# LineOut_Headphone.net
KiCad netlist of a schematic drawn in EAGLE
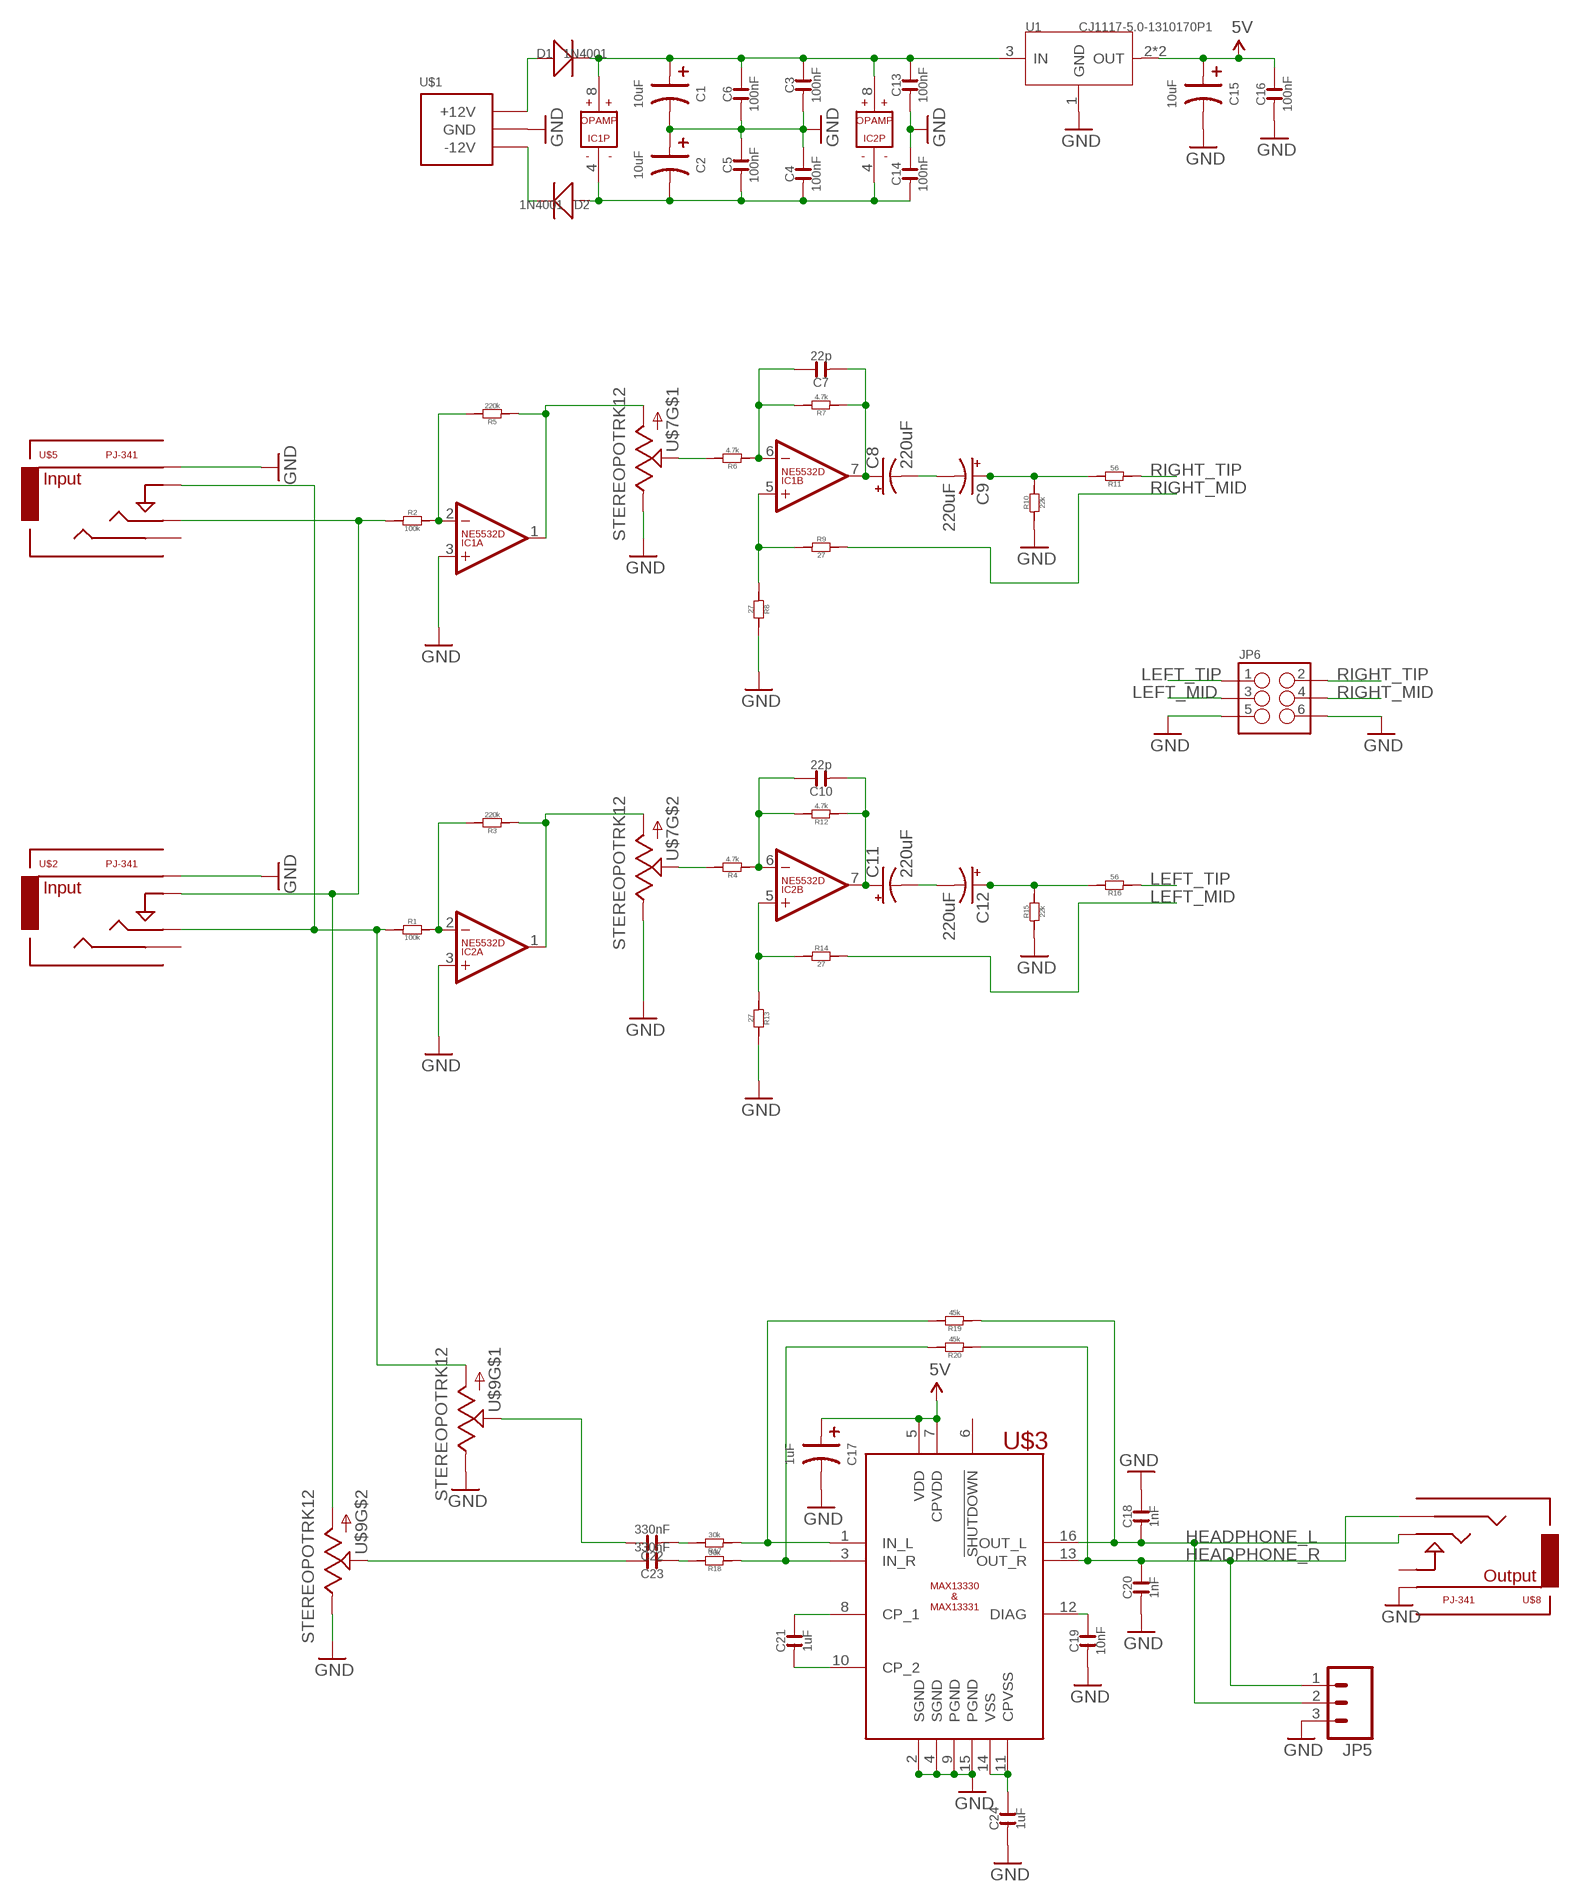
[diagram p0: schematic, sheet 1]

(export (version "E")
  (design (tool "Eeschema 10.0.6"))
  (components
    (comp (ref "C1")
      (value "10uF")
      (footprint "eagle-import:CASE-A_3216")
      (libsource (lib "eagle-import") (part "C-POLAR-A"))
    )
    (comp (ref "C2")
      (value "10uF")
      (footprint "eagle-import:CASE-A_3216")
      (libsource (lib "eagle-import") (part "C-POLAR-A"))
    )
    (comp (ref "C3")
      (value "100nF")
      (footprint "eagle-import:C0603")
      (libsource (lib "eagle-import") (part "C-0603"))
    )
    (comp (ref "C4")
      (value "100nF")
      (footprint "eagle-import:C0603")
      (libsource (lib "eagle-import") (part "C-0603"))
    )
    (comp (ref "C5")
      (value "100nF")
      (footprint "eagle-import:C0603")
      (libsource (lib "eagle-import") (part "C-0603"))
    )
    (comp (ref "C6")
      (value "100nF")
      (footprint "eagle-import:C0603")
      (libsource (lib "eagle-import") (part "C-0603"))
    )
    (comp (ref "C7")
      (value "22p")
      (footprint "eagle-import:C0603")
      (libsource (lib "eagle-import") (part "C-0603"))
    )
    (comp (ref "C8")
      (value "220uF")
      (footprint "eagle-import:153CLV-0505")
      (libsource (lib "eagle-import") (part "CPOL-US153CLV-0505"))
    )
    (comp (ref "C9")
      (value "220uF")
      (footprint "eagle-import:153CLV-0505")
      (libsource (lib "eagle-import") (part "CPOL-US153CLV-0505"))
    )
    (comp (ref "C10")
      (value "22p")
      (footprint "eagle-import:C0603")
      (libsource (lib "eagle-import") (part "C-0603"))
    )
    (comp (ref "C11")
      (value "220uF")
      (footprint "eagle-import:153CLV-0505")
      (libsource (lib "eagle-import") (part "CPOL-US153CLV-0505"))
    )
    (comp (ref "C12")
      (value "220uF")
      (footprint "eagle-import:153CLV-0505")
      (libsource (lib "eagle-import") (part "CPOL-US153CLV-0505"))
    )
    (comp (ref "C13")
      (value "100nF")
      (footprint "eagle-import:C0603")
      (libsource (lib "eagle-import") (part "C-0603"))
    )
    (comp (ref "C14")
      (value "100nF")
      (footprint "eagle-import:C0603")
      (libsource (lib "eagle-import") (part "C-0603"))
    )
    (comp (ref "C15")
      (value "10uF")
      (footprint "eagle-import:CASE-A_3216")
      (libsource (lib "eagle-import") (part "C-POLAR-A"))
    )
    (comp (ref "C16")
      (value "100nF")
      (footprint "eagle-import:C0603")
      (libsource (lib "eagle-import") (part "C-0603"))
    )
    (comp (ref "C17")
      (value "1uF")
      (footprint "eagle-import:CASE-A_3216")
      (libsource (lib "eagle-import") (part "C-POLAR-A"))
    )
    (comp (ref "C18")
      (value "1nF")
      (footprint "eagle-import:C0603")
      (libsource (lib "eagle-import") (part "C-0603"))
    )
    (comp (ref "C19")
      (value "10nF")
      (footprint "eagle-import:C0603")
      (libsource (lib "eagle-import") (part "C-0603"))
    )
    (comp (ref "C20")
      (value "1nF")
      (footprint "eagle-import:C0603")
      (libsource (lib "eagle-import") (part "C-0603"))
    )
    (comp (ref "C21")
      (value "1uF")
      (footprint "eagle-import:C0603")
      (libsource (lib "eagle-import") (part "C-0603"))
    )
    (comp (ref "C22")
      (value "330nF")
      (footprint "eagle-import:C0603")
      (libsource (lib "eagle-import") (part "C-0603"))
    )
    (comp (ref "C23")
      (value "330nF")
      (footprint "eagle-import:C0603")
      (libsource (lib "eagle-import") (part "C-0603"))
    )
    (comp (ref "C24")
      (value "1uF")
      (footprint "eagle-import:C0603")
      (libsource (lib "eagle-import") (part "C-0603"))
    )
    (comp (ref "D1")
      (value "1N4001")
      (footprint "eagle-import:SOD123")
      (libsource (lib "eagle-import") (part "D-SOD-123"))
    )
    (comp (ref "D2")
      (value "1N4001")
      (footprint "eagle-import:SOD123")
      (libsource (lib "eagle-import") (part "D-SOD-123"))
    )
    (comp (ref "IC1")
      (value "NE5532D")
      (footprint "eagle-import:SO08")
      (libsource (lib "eagle-import") (part "NE5532D"))
    )
    (comp (ref "IC2")
      (value "NE5532D")
      (footprint "eagle-import:SO08")
      (libsource (lib "eagle-import") (part "NE5532D"))
    )
    (comp (ref "JP5")
      (value "M03PTH")
      (footprint "eagle-import:1X03")
      (libsource (lib "eagle-import") (part "M03PTH"))
    )
    (comp (ref "JP6")
      (value "M03X2")
      (footprint "eagle-import:2X3-SHROUDED")
      (libsource (lib "eagle-import") (part "M03X2"))
    )
    (comp (ref "R1")
      (value "100k")
      (footprint "eagle-import:R0603")
      (libsource (lib "eagle-import") (part "R-0603"))
    )
    (comp (ref "R2")
      (value "100k")
      (footprint "eagle-import:R0603")
      (libsource (lib "eagle-import") (part "R-0603"))
    )
    (comp (ref "R3")
      (value "220k")
      (footprint "eagle-import:R0603")
      (libsource (lib "eagle-import") (part "R-0603"))
    )
    (comp (ref "R4")
      (value "4.7k")
      (footprint "eagle-import:R0603")
      (libsource (lib "eagle-import") (part "R-0603"))
    )
    (comp (ref "R5")
      (value "220k")
      (footprint "eagle-import:R0603")
      (libsource (lib "eagle-import") (part "R-0603"))
    )
    (comp (ref "R6")
      (value "4.7k")
      (footprint "eagle-import:R0603")
      (libsource (lib "eagle-import") (part "R-0603"))
    )
    (comp (ref "R7")
      (value "4.7k")
      (footprint "eagle-import:R0603")
      (libsource (lib "eagle-import") (part "R-0603"))
    )
    (comp (ref "R8")
      (value "27")
      (footprint "eagle-import:R0603")
      (libsource (lib "eagle-import") (part "R-0603"))
    )
    (comp (ref "R9")
      (value "27")
      (footprint "eagle-import:R0603")
      (libsource (lib "eagle-import") (part "R-0603"))
    )
    (comp (ref "R10")
      (value "22k")
      (footprint "eagle-import:R0603")
      (libsource (lib "eagle-import") (part "R-0603"))
    )
    (comp (ref "R11")
      (value "56")
      (footprint "eagle-import:R0603")
      (libsource (lib "eagle-import") (part "R-0603"))
    )
    (comp (ref "R12")
      (value "4.7k")
      (footprint "eagle-import:R0603")
      (libsource (lib "eagle-import") (part "R-0603"))
    )
    (comp (ref "R13")
      (value "27")
      (footprint "eagle-import:R0603")
      (libsource (lib "eagle-import") (part "R-0603"))
    )
    (comp (ref "R14")
      (value "27")
      (footprint "eagle-import:R0603")
      (libsource (lib "eagle-import") (part "R-0603"))
    )
    (comp (ref "R15")
      (value "22k")
      (footprint "eagle-import:R0603")
      (libsource (lib "eagle-import") (part "R-0603"))
    )
    (comp (ref "R16")
      (value "56")
      (footprint "eagle-import:R0603")
      (libsource (lib "eagle-import") (part "R-0603"))
    )
    (comp (ref "R17")
      (value "30k")
      (footprint "eagle-import:R0603")
      (libsource (lib "eagle-import") (part "R-0603"))
    )
    (comp (ref "R18")
      (value "30k")
      (footprint "eagle-import:R0603")
      (libsource (lib "eagle-import") (part "R-0603"))
    )
    (comp (ref "R19")
      (value "45k")
      (footprint "eagle-import:R0603")
      (libsource (lib "eagle-import") (part "R-0603"))
    )
    (comp (ref "R20")
      (value "45k")
      (footprint "eagle-import:R0603")
      (libsource (lib "eagle-import") (part "R-0603"))
    )
    (comp (ref "U$1")
      (value "POWER_SIMPLE10")
      (footprint "eagle-import:POWER_10")
      (libsource (lib "eagle-import") (part "POWER_SIMPLE10"))
    )
    (comp (ref "U$2")
      (value "PJ-341")
      (footprint "eagle-import:3.5MM-JACK-SWITCH-13MM-INPUT")
      (libsource (lib "eagle-import") (part "AUDIO-JACKINPUT"))
    )
    (comp (ref "U$3")
      (value "MAX13330")
      (footprint "eagle-import:QSOP16")
      (libsource (lib "eagle-import") (part "MAX13330"))
    )
    (comp (ref "U$5")
      (value "PJ-341")
      (footprint "eagle-import:3.5MM-JACK-SWITCH-13MM-INPUT")
      (libsource (lib "eagle-import") (part "AUDIO-JACKINPUT"))
    )
    (comp (ref "U$7")
      (value "STEREOPOTRK12")
      (footprint "eagle-import:RK12")
      (libsource (lib "eagle-import") (part "STEREOPOTRK12"))
    )
    (comp (ref "U$8")
      (value "PJ-341")
      (footprint "eagle-import:3.5MM-JACK-SWITCH-13MM-OUTPUT")
      (libsource (lib "eagle-import") (part "AUDIO-JACKOUTPUT"))
    )
    (comp (ref "U$9")
      (value "STEREOPOTRK12")
      (footprint "eagle-import:RK12")
      (libsource (lib "eagle-import") (part "STEREOPOTRK12"))
    )
    (comp (ref "U1")
      (value "CJ1117-5.0-1310170P1")
      (footprint "eagle-import:SOT223")
      (libsource (lib "eagle-import") (part "CJ1117-5.0-1310170P1"))
    )
  )
  (nets
    (net (code "1") (name "/HEADPHONE_L") (class "Default")
      (node (ref "C18") (pin "1") (pinfunction "1_1") (pintype "bidirectional"))
      (node (ref "JP5") (pin "2") (pinfunction "2_2") (pintype "passive"))
      (node (ref "R19") (pin "1") (pinfunction "1_1") (pintype "bidirectional"))
      (node (ref "U$3") (pin "16") (pinfunction "OUT_L_16") (pintype "bidirectional"))
      (node (ref "U$8") (pin "TIP@3") (pinfunction "TIP_TIP@3") (pintype "bidirectional"))
    )
    (net (code "2") (name "/HEADPHONE_R") (class "Default")
      (node (ref "C20") (pin "2") (pinfunction "2_2") (pintype "bidirectional"))
      (node (ref "JP5") (pin "1") (pinfunction "1_1") (pintype "passive"))
      (node (ref "R20") (pin "1") (pinfunction "1_1") (pintype "bidirectional"))
      (node (ref "U$3") (pin "13") (pinfunction "OUT_R_13") (pintype "bidirectional"))
      (node (ref "U$8") (pin "SECOND@3") (pinfunction "SECOND_SECOND@3") (pintype "bidirectional"))
    )
    (net (code "3") (name "/LEFT_MID") (class "Default")
      (node (ref "JP6") (pin "3") (pinfunction "3_3") (pintype "bidirectional"))
      (node (ref "R14") (pin "2") (pinfunction "2_2") (pintype "bidirectional"))
    )
    (net (code "4") (name "/LEFT_TIP") (class "Default")
      (node (ref "JP6") (pin "1") (pinfunction "1_1") (pintype "bidirectional"))
      (node (ref "R16") (pin "1") (pinfunction "1_1") (pintype "bidirectional"))
    )
    (net (code "5") (name "/RIGHT_MID") (class "Default")
      (node (ref "JP6") (pin "4") (pinfunction "4_4") (pintype "bidirectional"))
      (node (ref "R9") (pin "2") (pinfunction "2_2") (pintype "bidirectional"))
    )
    (net (code "6") (name "/RIGHT_TIP") (class "Default")
      (node (ref "JP6") (pin "2") (pinfunction "2_2") (pintype "bidirectional"))
      (node (ref "R11") (pin "1") (pinfunction "1_1") (pintype "bidirectional"))
    )
    (net (code "7") (name "5V") (class "Default")
      (node (ref "C15") (pin "+") (pinfunction "1_+") (pintype "bidirectional"))
      (node (ref "C16") (pin "2") (pinfunction "2_2") (pintype "bidirectional"))
      (node (ref "C17") (pin "+") (pinfunction "1_+") (pintype "bidirectional"))
      (node (ref "U$3") (pin "5") (pinfunction "VDD_5") (pintype "bidirectional"))
      (node (ref "U$3") (pin "7") (pinfunction "CPVDD_7") (pintype "bidirectional"))
      (node (ref "U1") (pin "2") (pinfunction "OUT_2") (pintype "bidirectional"))
      (node (ref "U1") (pin "TER") (pinfunction "OUT_TER") (pintype "bidirectional"))
    )
    (net (code "8") (name "GND") (class "Default")
      (node (ref "C1") (pin "-") (pinfunction "2_-") (pintype "bidirectional"))
      (node (ref "C13") (pin "1") (pinfunction "1_1") (pintype "bidirectional"))
      (node (ref "C14") (pin "2") (pinfunction "2_2") (pintype "bidirectional"))
      (node (ref "C15") (pin "-") (pinfunction "2_-") (pintype "bidirectional"))
      (node (ref "C16") (pin "1") (pinfunction "1_1") (pintype "bidirectional"))
      (node (ref "C17") (pin "-") (pinfunction "2_-") (pintype "bidirectional"))
      (node (ref "C18") (pin "2") (pinfunction "2_2") (pintype "bidirectional"))
      (node (ref "C19") (pin "1") (pinfunction "1_1") (pintype "bidirectional"))
      (node (ref "C2") (pin "+") (pinfunction "1_+") (pintype "bidirectional"))
      (node (ref "C20") (pin "1") (pinfunction "1_1") (pintype "bidirectional"))
      (node (ref "C24") (pin "1") (pinfunction "1_1") (pintype "bidirectional"))
      (node (ref "C3") (pin "1") (pinfunction "1_1") (pintype "bidirectional"))
      (node (ref "C4") (pin "2") (pinfunction "2_2") (pintype "bidirectional"))
      (node (ref "C5") (pin "2") (pinfunction "2_2") (pintype "bidirectional"))
      (node (ref "C6") (pin "1") (pinfunction "1_1") (pintype "bidirectional"))
      (node (ref "IC1") (pin "3") (pinfunction "+IN_3") (pintype "input"))
      (node (ref "IC2") (pin "3") (pinfunction "+IN_3") (pintype "input"))
      (node (ref "JP5") (pin "3") (pinfunction "3_3") (pintype "passive"))
      (node (ref "JP6") (pin "5") (pinfunction "5_5") (pintype "bidirectional"))
      (node (ref "JP6") (pin "6") (pinfunction "6_6") (pintype "bidirectional"))
      (node (ref "R10") (pin "1") (pinfunction "1_1") (pintype "bidirectional"))
      (node (ref "R13") (pin "2") (pinfunction "2_2") (pintype "bidirectional"))
      (node (ref "R15") (pin "1") (pinfunction "1_1") (pintype "bidirectional"))
      (node (ref "R8") (pin "2") (pinfunction "2_2") (pintype "bidirectional"))
      (node (ref "U$1") (pin "3") (pinfunction "GND_3") (pintype "bidirectional"))
      (node (ref "U$1") (pin "4") (pinfunction "GND_4") (pintype "bidirectional"))
      (node (ref "U$1") (pin "5") (pinfunction "GND_5") (pintype "bidirectional"))
      (node (ref "U$1") (pin "6") (pinfunction "GND_6") (pintype "bidirectional"))
      (node (ref "U$1") (pin "7") (pinfunction "GND_7") (pintype "bidirectional"))
      (node (ref "U$1") (pin "8") (pinfunction "GND_8") (pintype "bidirectional"))
      (node (ref "U$2") (pin "RING@3") (pinfunction "RING_RING@3") (pintype "bidirectional"))
      (node (ref "U$3") (pin "15") (pinfunction "PGND_15") (pintype "bidirectional"))
      (node (ref "U$3") (pin "2") (pinfunction "SGND_2") (pintype "bidirectional"))
      (node (ref "U$3") (pin "4") (pinfunction "SGND_4") (pintype "bidirectional"))
      (node (ref "U$3") (pin "9") (pinfunction "PGND_9") (pintype "bidirectional"))
      (node (ref "U$5") (pin "RING@3") (pinfunction "RING_RING@3") (pintype "bidirectional"))
      (node (ref "U$7") (pin "R1_1") (pinfunction "E_R1_1") (pintype "passive"))
      (node (ref "U$7") (pin "R2_1") (pinfunction "E_R2_1") (pintype "passive"))
      (node (ref "U$8") (pin "RING@3") (pinfunction "RING_RING@3") (pintype "bidirectional"))
      (node (ref "U$9") (pin "R1_1") (pinfunction "E_R1_1") (pintype "passive"))
      (node (ref "U$9") (pin "R2_1") (pinfunction "E_R2_1") (pintype "passive"))
      (node (ref "U1") (pin "1") (pinfunction "GND_1") (pintype "bidirectional"))
    )
    (net (code "9") (name "Net-(C1-1)") (class "Default")
      (node (ref "C1") (pin "+") (pinfunction "1_+") (pintype "bidirectional"))
      (node (ref "C13") (pin "2") (pinfunction "2_2") (pintype "bidirectional"))
      (node (ref "C3") (pin "2") (pinfunction "2_2") (pintype "bidirectional"))
      (node (ref "C6") (pin "2") (pinfunction "2_2") (pintype "bidirectional"))
      (node (ref "D1") (pin "-") (pinfunction "-_-") (pintype "passive"))
      (node (ref "IC1") (pin "8") (pinfunction "V+_8") (pintype "power_in"))
      (node (ref "IC2") (pin "8") (pinfunction "V+_8") (pintype "power_in"))
      (node (ref "U1") (pin "3") (pinfunction "IN_3") (pintype "bidirectional"))
    )
    (net (code "10") (name "Net-(C2-2)") (class "Default")
      (node (ref "C14") (pin "1") (pinfunction "1_1") (pintype "bidirectional"))
      (node (ref "C2") (pin "-") (pinfunction "2_-") (pintype "bidirectional"))
      (node (ref "C4") (pin "1") (pinfunction "1_1") (pintype "bidirectional"))
      (node (ref "C5") (pin "1") (pinfunction "1_1") (pintype "bidirectional"))
      (node (ref "D2") (pin "+") (pinfunction "+_+") (pintype "passive"))
      (node (ref "IC1") (pin "4") (pinfunction "V-_4") (pintype "power_in"))
      (node (ref "IC2") (pin "4") (pinfunction "V-_4") (pintype "power_in"))
    )
    (net (code "11") (name "Net-(C8-Pad-)") (class "Default")
      (node (ref "C8") (pin "-") (pinfunction "-_-") (pintype "passive"))
      (node (ref "C9") (pin "-") (pinfunction "-_-") (pintype "passive"))
    )
    (net (code "12") (name "Net-(C9-Pad+)") (class "Default")
      (node (ref "C9") (pin "+") (pinfunction "+_+") (pintype "passive"))
      (node (ref "R10") (pin "2") (pinfunction "2_2") (pintype "bidirectional"))
      (node (ref "R11") (pin "2") (pinfunction "2_2") (pintype "bidirectional"))
    )
    (net (code "13") (name "Net-(C11-Pad-)") (class "Default")
      (node (ref "C11") (pin "-") (pinfunction "-_-") (pintype "passive"))
      (node (ref "C12") (pin "-") (pinfunction "-_-") (pintype "passive"))
    )
    (net (code "14") (name "Net-(C12-Pad+)") (class "Default")
      (node (ref "C12") (pin "+") (pinfunction "+_+") (pintype "passive"))
      (node (ref "R15") (pin "2") (pinfunction "2_2") (pintype "bidirectional"))
      (node (ref "R16") (pin "2") (pinfunction "2_2") (pintype "bidirectional"))
    )
    (net (code "15") (name "Net-(C22-Pad1)") (class "Default")
      (node (ref "C22") (pin "1") (pinfunction "1_1") (pintype "bidirectional"))
      (node (ref "R17") (pin "2") (pinfunction "2_2") (pintype "bidirectional"))
    )
    (net (code "16") (name "Net-(C23-Pad1)") (class "Default")
      (node (ref "C23") (pin "1") (pinfunction "1_1") (pintype "bidirectional"))
      (node (ref "R18") (pin "2") (pinfunction "2_2") (pintype "bidirectional"))
    )
    (net (code "17") (name "Net-(D1-Pad+)") (class "Default")
      (node (ref "D1") (pin "+") (pinfunction "+_+") (pintype "passive"))
      (node (ref "U$1") (pin "10") (pinfunction "+12V_10") (pintype "bidirectional"))
      (node (ref "U$1") (pin "9") (pinfunction "+12V_9") (pintype "bidirectional"))
    )
    (net (code "18") (name "Net-(D2-Pad-)") (class "Default")
      (node (ref "D2") (pin "-") (pinfunction "-_-") (pintype "passive"))
      (node (ref "U$1") (pin "1") (pinfunction "-12V_1") (pintype "bidirectional"))
      (node (ref "U$1") (pin "2") (pinfunction "-12V_2") (pintype "bidirectional"))
    )
    (net (code "19") (name "Net-(IC1A--IN)") (class "Default")
      (node (ref "IC1") (pin "2") (pinfunction "-IN_2") (pintype "input"))
      (node (ref "R2") (pin "2") (pinfunction "2_2") (pintype "bidirectional"))
      (node (ref "R5") (pin "2") (pinfunction "2_2") (pintype "bidirectional"))
    )
    (net (code "20") (name "Net-(IC1A-OUT)") (class "Default")
      (node (ref "IC1") (pin "1") (pinfunction "OUT_1") (pintype "output"))
      (node (ref "R5") (pin "1") (pinfunction "1_1") (pintype "bidirectional"))
      (node (ref "U$7") (pin "R1_3") (pinfunction "A_R1_3") (pintype "passive"))
    )
    (net (code "21") (name "Net-(IC1B-+IN)") (class "Default")
      (node (ref "IC1") (pin "5") (pinfunction "+IN_5") (pintype "input"))
      (node (ref "R8") (pin "1") (pinfunction "1_1") (pintype "bidirectional"))
      (node (ref "R9") (pin "1") (pinfunction "1_1") (pintype "bidirectional"))
    )
    (net (code "22") (name "Net-(IC1B--IN)") (class "Default")
      (node (ref "C7") (pin "2") (pinfunction "2_2") (pintype "bidirectional"))
      (node (ref "IC1") (pin "6") (pinfunction "-IN_6") (pintype "input"))
      (node (ref "R6") (pin "1") (pinfunction "1_1") (pintype "bidirectional"))
      (node (ref "R7") (pin "2") (pinfunction "2_2") (pintype "bidirectional"))
    )
    (net (code "23") (name "Net-(IC1B-OUT)") (class "Default")
      (node (ref "C7") (pin "1") (pinfunction "1_1") (pintype "bidirectional"))
      (node (ref "C8") (pin "+") (pinfunction "+_+") (pintype "passive"))
      (node (ref "IC1") (pin "7") (pinfunction "OUT_7") (pintype "output"))
      (node (ref "R7") (pin "1") (pinfunction "1_1") (pintype "bidirectional"))
    )
    (net (code "24") (name "Net-(IC2A--IN)") (class "Default")
      (node (ref "IC2") (pin "2") (pinfunction "-IN_2") (pintype "input"))
      (node (ref "R1") (pin "2") (pinfunction "2_2") (pintype "bidirectional"))
      (node (ref "R3") (pin "2") (pinfunction "2_2") (pintype "bidirectional"))
    )
    (net (code "25") (name "Net-(IC2A-OUT)") (class "Default")
      (node (ref "IC2") (pin "1") (pinfunction "OUT_1") (pintype "output"))
      (node (ref "R3") (pin "1") (pinfunction "1_1") (pintype "bidirectional"))
      (node (ref "U$7") (pin "R2_3") (pinfunction "A_R2_3") (pintype "passive"))
    )
    (net (code "26") (name "Net-(IC2B-+IN)") (class "Default")
      (node (ref "IC2") (pin "5") (pinfunction "+IN_5") (pintype "input"))
      (node (ref "R13") (pin "1") (pinfunction "1_1") (pintype "bidirectional"))
      (node (ref "R14") (pin "1") (pinfunction "1_1") (pintype "bidirectional"))
    )
    (net (code "27") (name "Net-(IC2B--IN)") (class "Default")
      (node (ref "C10") (pin "2") (pinfunction "2_2") (pintype "bidirectional"))
      (node (ref "IC2") (pin "6") (pinfunction "-IN_6") (pintype "input"))
      (node (ref "R12") (pin "2") (pinfunction "2_2") (pintype "bidirectional"))
      (node (ref "R4") (pin "1") (pinfunction "1_1") (pintype "bidirectional"))
    )
    (net (code "28") (name "Net-(IC2B-OUT)") (class "Default")
      (node (ref "C10") (pin "1") (pinfunction "1_1") (pintype "bidirectional"))
      (node (ref "C11") (pin "+") (pinfunction "+_+") (pintype "passive"))
      (node (ref "IC2") (pin "7") (pinfunction "OUT_7") (pintype "output"))
      (node (ref "R12") (pin "1") (pinfunction "1_1") (pintype "bidirectional"))
    )
    (net (code "29") (name "Net-(U$2-SWITCH)") (class "Default")
      (node (ref "R2") (pin "1") (pinfunction "1_1") (pintype "bidirectional"))
      (node (ref "U$2") (pin "SWITCH@3") (pinfunction "SWITCH_SWITCH@3") (pintype "bidirectional"))
      (node (ref "U$5") (pin "TIP@3") (pinfunction "TIP_TIP@3") (pintype "bidirectional"))
      (node (ref "U$9") (pin "R2_3") (pinfunction "A_R2_3") (pintype "passive"))
    )
    (net (code "30") (name "Net-(U$2-TIP)") (class "Default")
      (node (ref "R1") (pin "1") (pinfunction "1_1") (pintype "bidirectional"))
      (node (ref "U$2") (pin "TIP@3") (pinfunction "TIP_TIP@3") (pintype "bidirectional"))
      (node (ref "U$5") (pin "SWITCH@3") (pinfunction "SWITCH_SWITCH@3") (pintype "bidirectional"))
      (node (ref "U$9") (pin "R1_3") (pinfunction "A_R1_3") (pintype "passive"))
    )
    (net (code "31") (name "Net-(U$3-CPVSS)") (class "Default")
      (node (ref "C24") (pin "2") (pinfunction "2_2") (pintype "bidirectional"))
      (node (ref "U$3") (pin "11") (pinfunction "CPVSS_11") (pintype "bidirectional"))
      (node (ref "U$3") (pin "14") (pinfunction "VSS_14") (pintype "bidirectional"))
    )
    (net (code "32") (name "Net-(U$3-CP_1)") (class "Default")
      (node (ref "C21") (pin "2") (pinfunction "2_2") (pintype "bidirectional"))
      (node (ref "U$3") (pin "8") (pinfunction "CP_1_8") (pintype "bidirectional"))
    )
    (net (code "33") (name "Net-(U$3-CP_2)") (class "Default")
      (node (ref "C21") (pin "1") (pinfunction "1_1") (pintype "bidirectional"))
      (node (ref "U$3") (pin "10") (pinfunction "CP_2_10") (pintype "bidirectional"))
    )
    (net (code "34") (name "Net-(U$3-DIAG)") (class "Default")
      (node (ref "C19") (pin "2") (pinfunction "2_2") (pintype "bidirectional"))
      (node (ref "U$3") (pin "12") (pinfunction "DIAG_12") (pintype "bidirectional"))
    )
    (net (code "35") (name "Net-(U$3-IN_L)") (class "Default")
      (node (ref "R17") (pin "1") (pinfunction "1_1") (pintype "bidirectional"))
      (node (ref "R19") (pin "2") (pinfunction "2_2") (pintype "bidirectional"))
      (node (ref "U$3") (pin "1") (pinfunction "IN_L_1") (pintype "bidirectional"))
    )
    (net (code "36") (name "Net-(U$3-IN_R)") (class "Default")
      (node (ref "R18") (pin "1") (pinfunction "1_1") (pintype "bidirectional"))
      (node (ref "R20") (pin "2") (pinfunction "2_2") (pintype "bidirectional"))
      (node (ref "U$3") (pin "3") (pinfunction "IN_R_3") (pintype "bidirectional"))
    )
    (net (code "37") (name "Net-(U$7A-S)") (class "Default")
      (node (ref "R6") (pin "2") (pinfunction "2_2") (pintype "bidirectional"))
      (node (ref "U$7") (pin "R1_2") (pinfunction "S_R1_2") (pintype "passive"))
    )
    (net (code "38") (name "Net-(U$7B-S)") (class "Default")
      (node (ref "R4") (pin "2") (pinfunction "2_2") (pintype "bidirectional"))
      (node (ref "U$7") (pin "R2_2") (pinfunction "S_R2_2") (pintype "passive"))
    )
    (net (code "39") (name "Net-(U$9A-S)") (class "Default")
      (node (ref "C22") (pin "2") (pinfunction "2_2") (pintype "bidirectional"))
      (node (ref "U$9") (pin "R1_2") (pinfunction "S_R1_2") (pintype "passive"))
    )
    (net (code "40") (name "Net-(U$9B-S)") (class "Default")
      (node (ref "C23") (pin "2") (pinfunction "2_2") (pintype "bidirectional"))
      (node (ref "U$9") (pin "R2_2") (pinfunction "S_R2_2") (pintype "passive"))
    )
    (net (code "41") (name "unconnected-(U$2-SECOND-PadSECOND@3)") (class "Default")
      (node (ref "U$2") (pin "SECOND@3") (pinfunction "SECOND_SECOND@3") (pintype "bidirectional"))
    )
    (net (code "42") (name "unconnected-(U$3-~{SHUTDOWN}-Pad6)") (class "Default")
      (node (ref "U$3") (pin "6") (pinfunction "~{SHUTDOWN}_6") (pintype "bidirectional"))
    )
    (net (code "43") (name "unconnected-(U$5-SECOND-PadSECOND@3)") (class "Default")
      (node (ref "U$5") (pin "SECOND@3") (pinfunction "SECOND_SECOND@3") (pintype "bidirectional"))
    )
    (net (code "44") (name "unconnected-(U$8-SWITCH-PadSWITCH@3)") (class "Default")
      (node (ref "U$8") (pin "SWITCH@3") (pinfunction "SWITCH_SWITCH@3") (pintype "bidirectional"))
    )
  )
)
